# ATTiny84-RFM95W-BME280.net
KiCad netlist of a schematic drawn in EAGLE
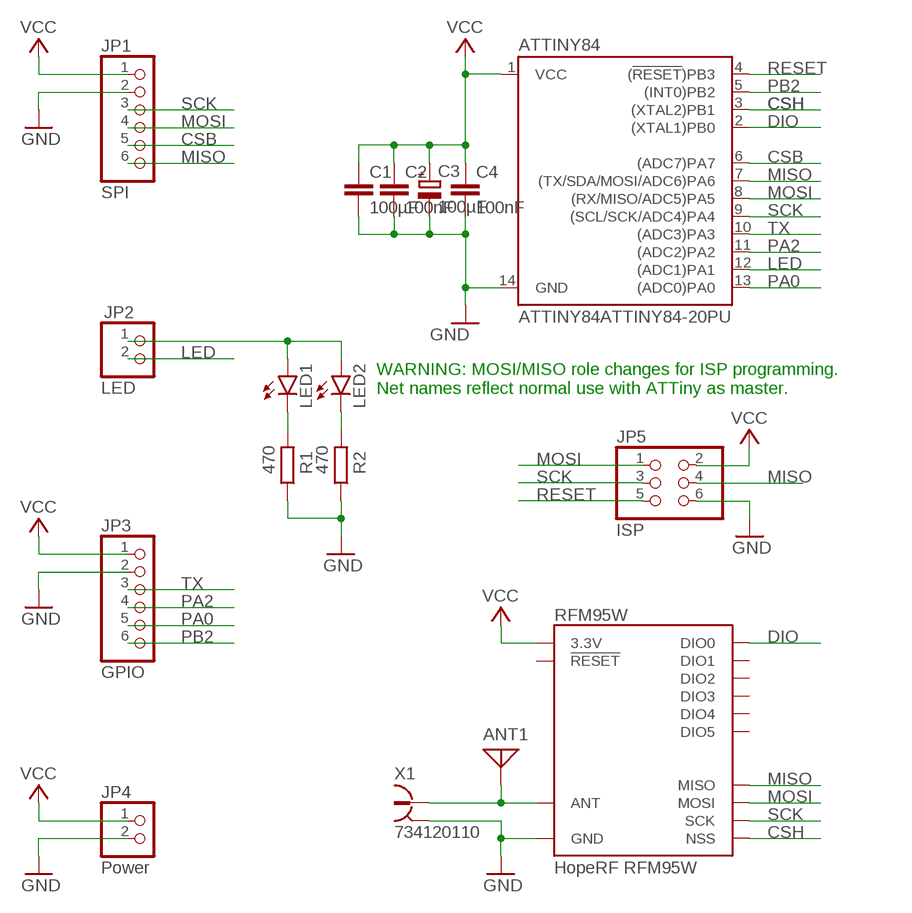
[diagram p0: schematic, sheet 1]

(export (version "E")
  (design (tool "Eeschema 10.0.6"))
  (components
    (comp (ref "ANT1")
      (value "ANTENNA")
      (footprint "eagle-import:PAD-01")
      (libsource (lib "eagle-import") (part "ANTENNA"))
    )
    (comp (ref "ATTINY84")
      (value "ATTINY84ATTINY84-20PU")
      (footprint "eagle-import:DIP14")
      (libsource (lib "eagle-import") (part "ATTINY84ATTINY84-20PU"))
    )
    (comp (ref "C1")
      (value "100µF")
      (footprint "eagle-import:C0805")
      (libsource (lib "eagle-import") (part "C-EUC0805"))
    )
    (comp (ref "C2")
      (value "100nF")
      (footprint "eagle-import:C0805")
      (libsource (lib "eagle-import") (part "C-EUC0805"))
    )
    (comp (ref "C3")
      (value "100µF")
      (footprint "eagle-import:E2,5-6")
      (libsource (lib "eagle-import") (part "CPOL-EUE2.5-6"))
    )
    (comp (ref "C4")
      (value "100nF")
      (footprint "eagle-import:C050-050X075")
      (libsource (lib "eagle-import") (part "C-EU050-050X075"))
    )
    (comp (ref "JP1")
      (value "SPI")
      (footprint "eagle-import:1X06")
      (libsource (lib "eagle-import") (part "PINHD-1X6"))
    )
    (comp (ref "JP2")
      (value "LED")
      (footprint "eagle-import:1X02")
      (libsource (lib "eagle-import") (part "PINHD-1X2"))
    )
    (comp (ref "JP3")
      (value "GPIO")
      (footprint "eagle-import:1X06")
      (libsource (lib "eagle-import") (part "PINHD-1X6"))
    )
    (comp (ref "JP4")
      (value "Power")
      (footprint "eagle-import:1X02")
      (libsource (lib "eagle-import") (part "PINHD-1X2"))
    )
    (comp (ref "JP5")
      (value "ISP")
      (footprint "eagle-import:2X03")
      (libsource (lib "eagle-import") (part "PINHD-2X3"))
    )
    (comp (ref "LED1")
      (value "LEDCHIP-LED0805")
      (footprint "eagle-import:CHIP-LED0805")
      (libsource (lib "eagle-import") (part "LEDCHIP-LED0805"))
    )
    (comp (ref "LED2")
      (value "LED3MM")
      (footprint "eagle-import:LED3MM")
      (libsource (lib "eagle-import") (part "LED3MM"))
    )
    (comp (ref "R1")
      (value "470")
      (footprint "eagle-import:R0805")
      (libsource (lib "eagle-import") (part "R-EU_R0805"))
    )
    (comp (ref "R2")
      (value "470")
      (footprint "eagle-import:0207_12")
      (libsource (lib "eagle-import") (part "R-EU_0207/12"))
    )
    (comp (ref "RFM95W")
      (value "RFM95W")
      (footprint "eagle-import:RFM95_96_97_98W")
      (fields (field (name "PROD_NAME") "HopeRF RFM95W"))
      (libsource (lib "eagle-import") (part "RFM95W"))
    )
    (comp (ref "X1")
      (value "734120110")
      (footprint "eagle-import:734120110")
      (libsource (lib "eagle-import") (part "734120110"))
    )
  )
  (nets
    (net (code "1") (name "/CSB") (class "Default")
      (node (ref "ATTINY84") (pin "6") (pinfunction "(ADC7)PA7_6") (pintype "bidirectional"))
      (node (ref "JP1") (pin "5") (pinfunction "5_5") (pintype "passive"))
    )
    (net (code "2") (name "/CSH") (class "Default")
      (node (ref "ATTINY84") (pin "3") (pinfunction "(XTAL2)PB1_3") (pintype "bidirectional"))
      (node (ref "RFM95W") (pin "NSS") (pinfunction "NSS_NSS") (pintype "bidirectional"))
    )
    (net (code "3") (name "/DIO") (class "Default")
      (node (ref "ATTINY84") (pin "2") (pinfunction "(XTAL1)PB0_2") (pintype "bidirectional"))
      (node (ref "RFM95W") (pin "DIO0") (pinfunction "DIO0_DIO0") (pintype "bidirectional"))
    )
    (net (code "4") (name "/LED") (class "Default")
      (node (ref "ATTINY84") (pin "12") (pinfunction "(ADC1)PA1_12") (pintype "bidirectional"))
      (node (ref "JP2") (pin "2") (pinfunction "2_2") (pintype "passive"))
    )
    (net (code "5") (name "/MISO") (class "Default")
      (node (ref "ATTINY84") (pin "7") (pinfunction "(TX/SDA/MOSI/ADC6)PA6_7") (pintype "bidirectional"))
      (node (ref "JP1") (pin "6") (pinfunction "6_6") (pintype "passive"))
      (node (ref "JP5") (pin "4") (pinfunction "4_4") (pintype "passive"))
      (node (ref "RFM95W") (pin "MISO") (pinfunction "MISO_MISO") (pintype "bidirectional"))
    )
    (net (code "6") (name "/MOSI") (class "Default")
      (node (ref "ATTINY84") (pin "8") (pinfunction "(RX/MISO/ADC5)PA5_8") (pintype "bidirectional"))
      (node (ref "JP1") (pin "4") (pinfunction "4_4") (pintype "passive"))
      (node (ref "JP5") (pin "1") (pinfunction "1_1") (pintype "passive"))
      (node (ref "RFM95W") (pin "MOSI") (pinfunction "MOSI_MOSI") (pintype "bidirectional"))
    )
    (net (code "7") (name "/PA0") (class "Default")
      (node (ref "ATTINY84") (pin "13") (pinfunction "(ADC0)PA0_13") (pintype "bidirectional"))
      (node (ref "JP3") (pin "5") (pinfunction "5_5") (pintype "passive"))
    )
    (net (code "8") (name "/PA2") (class "Default")
      (node (ref "ATTINY84") (pin "11") (pinfunction "(ADC2)PA2_11") (pintype "bidirectional"))
      (node (ref "JP3") (pin "4") (pinfunction "4_4") (pintype "passive"))
    )
    (net (code "9") (name "/PB2") (class "Default")
      (node (ref "ATTINY84") (pin "5") (pinfunction "(INT0)PB2_5") (pintype "bidirectional"))
      (node (ref "JP3") (pin "6") (pinfunction "6_6") (pintype "passive"))
    )
    (net (code "10") (name "/RESET") (class "Default")
      (node (ref "ATTINY84") (pin "4") (pinfunction "(~{RESET})PB3_4") (pintype "bidirectional"))
      (node (ref "JP5") (pin "5") (pinfunction "5_5") (pintype "passive"))
    )
    (net (code "11") (name "/SCK") (class "Default")
      (node (ref "ATTINY84") (pin "9") (pinfunction "(SCL/SCK/ADC4)PA4_9") (pintype "bidirectional"))
      (node (ref "JP1") (pin "3") (pinfunction "3_3") (pintype "passive"))
      (node (ref "JP5") (pin "3") (pinfunction "3_3") (pintype "passive"))
      (node (ref "RFM95W") (pin "SCK") (pinfunction "SCK_SCK") (pintype "bidirectional"))
    )
    (net (code "12") (name "/TX") (class "Default")
      (node (ref "ATTINY84") (pin "10") (pinfunction "(ADC3)PA3_10") (pintype "bidirectional"))
      (node (ref "JP3") (pin "3") (pinfunction "3_3") (pintype "passive"))
    )
    (net (code "13") (name "GND") (class "Default")
      (node (ref "ATTINY84") (pin "14") (pinfunction "GND_14") (pintype "bidirectional"))
      (node (ref "C1") (pin "2") (pinfunction "2_2") (pintype "passive"))
      (node (ref "C2") (pin "2") (pinfunction "2_2") (pintype "passive"))
      (node (ref "C3") (pin "-") (pinfunction "-_-") (pintype "passive"))
      (node (ref "C4") (pin "2") (pinfunction "2_2") (pintype "passive"))
      (node (ref "JP1") (pin "2") (pinfunction "2_2") (pintype "passive"))
      (node (ref "JP3") (pin "2") (pinfunction "2_2") (pintype "passive"))
      (node (ref "JP4") (pin "2") (pinfunction "2_2") (pintype "passive"))
      (node (ref "JP5") (pin "6") (pinfunction "6_6") (pintype "passive"))
      (node (ref "R1") (pin "1") (pinfunction "1_1") (pintype "passive"))
      (node (ref "R2") (pin "1") (pinfunction "1_1") (pintype "passive"))
      (node (ref "RFM95W") (pin "GND@1") (pinfunction "GND_GND@1") (pintype "bidirectional"))
      (node (ref "RFM95W") (pin "GND@2") (pinfunction "GND_GND@2") (pintype "bidirectional"))
      (node (ref "RFM95W") (pin "GND@3") (pinfunction "GND_GND@3") (pintype "bidirectional"))
      (node (ref "X1") (pin "S@1") (pinfunction "2_S@1") (pintype "passive"))
      (node (ref "X1") (pin "S@2") (pinfunction "2_S@2") (pintype "passive"))
      (node (ref "X1") (pin "S@3") (pinfunction "2_S@3") (pintype "passive"))
    )
    (net (code "14") (name "Net-(ANT1-Pad1)") (class "Default")
      (node (ref "ANT1") (pin "1") (pinfunction "1_1") (pintype "output"))
      (node (ref "RFM95W") (pin "ANT") (pinfunction "ANT_ANT") (pintype "bidirectional"))
      (node (ref "X1") (pin "1") (pinfunction "1_1") (pintype "passive"))
    )
    (net (code "15") (name "Net-(JP2-Pad1)") (class "Default")
      (node (ref "JP2") (pin "1") (pinfunction "1_1") (pintype "passive"))
      (node (ref "LED1") (pin "A") (pinfunction "A_A") (pintype "passive"))
      (node (ref "LED2") (pin "A") (pinfunction "A_A") (pintype "passive"))
    )
    (net (code "16") (name "Net-(LED1-PadC)") (class "Default")
      (node (ref "LED1") (pin "C") (pinfunction "C_C") (pintype "passive"))
      (node (ref "R1") (pin "2") (pinfunction "2_2") (pintype "passive"))
    )
    (net (code "17") (name "Net-(LED2-C)") (class "Default")
      (node (ref "LED2") (pin "K") (pinfunction "C_K") (pintype "passive"))
      (node (ref "R2") (pin "2") (pinfunction "2_2") (pintype "passive"))
    )
    (net (code "18") (name "VCC") (class "Default")
      (node (ref "ATTINY84") (pin "1") (pinfunction "VCC_1") (pintype "bidirectional"))
      (node (ref "C1") (pin "1") (pinfunction "1_1") (pintype "passive"))
      (node (ref "C2") (pin "1") (pinfunction "1_1") (pintype "passive"))
      (node (ref "C3") (pin "+") (pinfunction "+_+") (pintype "passive"))
      (node (ref "C4") (pin "1") (pinfunction "1_1") (pintype "passive"))
      (node (ref "JP1") (pin "1") (pinfunction "1_1") (pintype "passive"))
      (node (ref "JP3") (pin "1") (pinfunction "1_1") (pintype "passive"))
      (node (ref "JP4") (pin "1") (pinfunction "1_1") (pintype "passive"))
      (node (ref "JP5") (pin "2") (pinfunction "2_2") (pintype "passive"))
      (node (ref "RFM95W") (pin "3.3V") (pinfunction "3.3V_3.3V") (pintype "bidirectional"))
    )
    (net (code "19") (name "unconnected-(RFM95W-PadDIO1)") (class "Default")
      (node (ref "RFM95W") (pin "DIO1") (pinfunction "DIO1_DIO1") (pintype "bidirectional"))
    )
    (net (code "20") (name "unconnected-(RFM95W-PadDIO2)") (class "Default")
      (node (ref "RFM95W") (pin "DIO2") (pinfunction "DIO2_DIO2") (pintype "bidirectional"))
    )
    (net (code "21") (name "unconnected-(RFM95W-PadDIO3)") (class "Default")
      (node (ref "RFM95W") (pin "DIO3") (pinfunction "DIO3_DIO3") (pintype "bidirectional"))
    )
    (net (code "22") (name "unconnected-(RFM95W-PadDIO4)") (class "Default")
      (node (ref "RFM95W") (pin "DIO4") (pinfunction "DIO4_DIO4") (pintype "bidirectional"))
    )
    (net (code "23") (name "unconnected-(RFM95W-PadDIO5)") (class "Default")
      (node (ref "RFM95W") (pin "DIO5") (pinfunction "DIO5_DIO5") (pintype "bidirectional"))
    )
    (net (code "24") (name "unconnected-(RFM95W-~{RESET}-Pad!RESET)") (class "Default")
      (node (ref "RFM95W") (pin "!RESET") (pinfunction "~{RESET}_!RESET") (pintype "bidirectional"))
    )
  )
)
